# schema.net
KiCad netlist of a schematic drawn in EAGLE
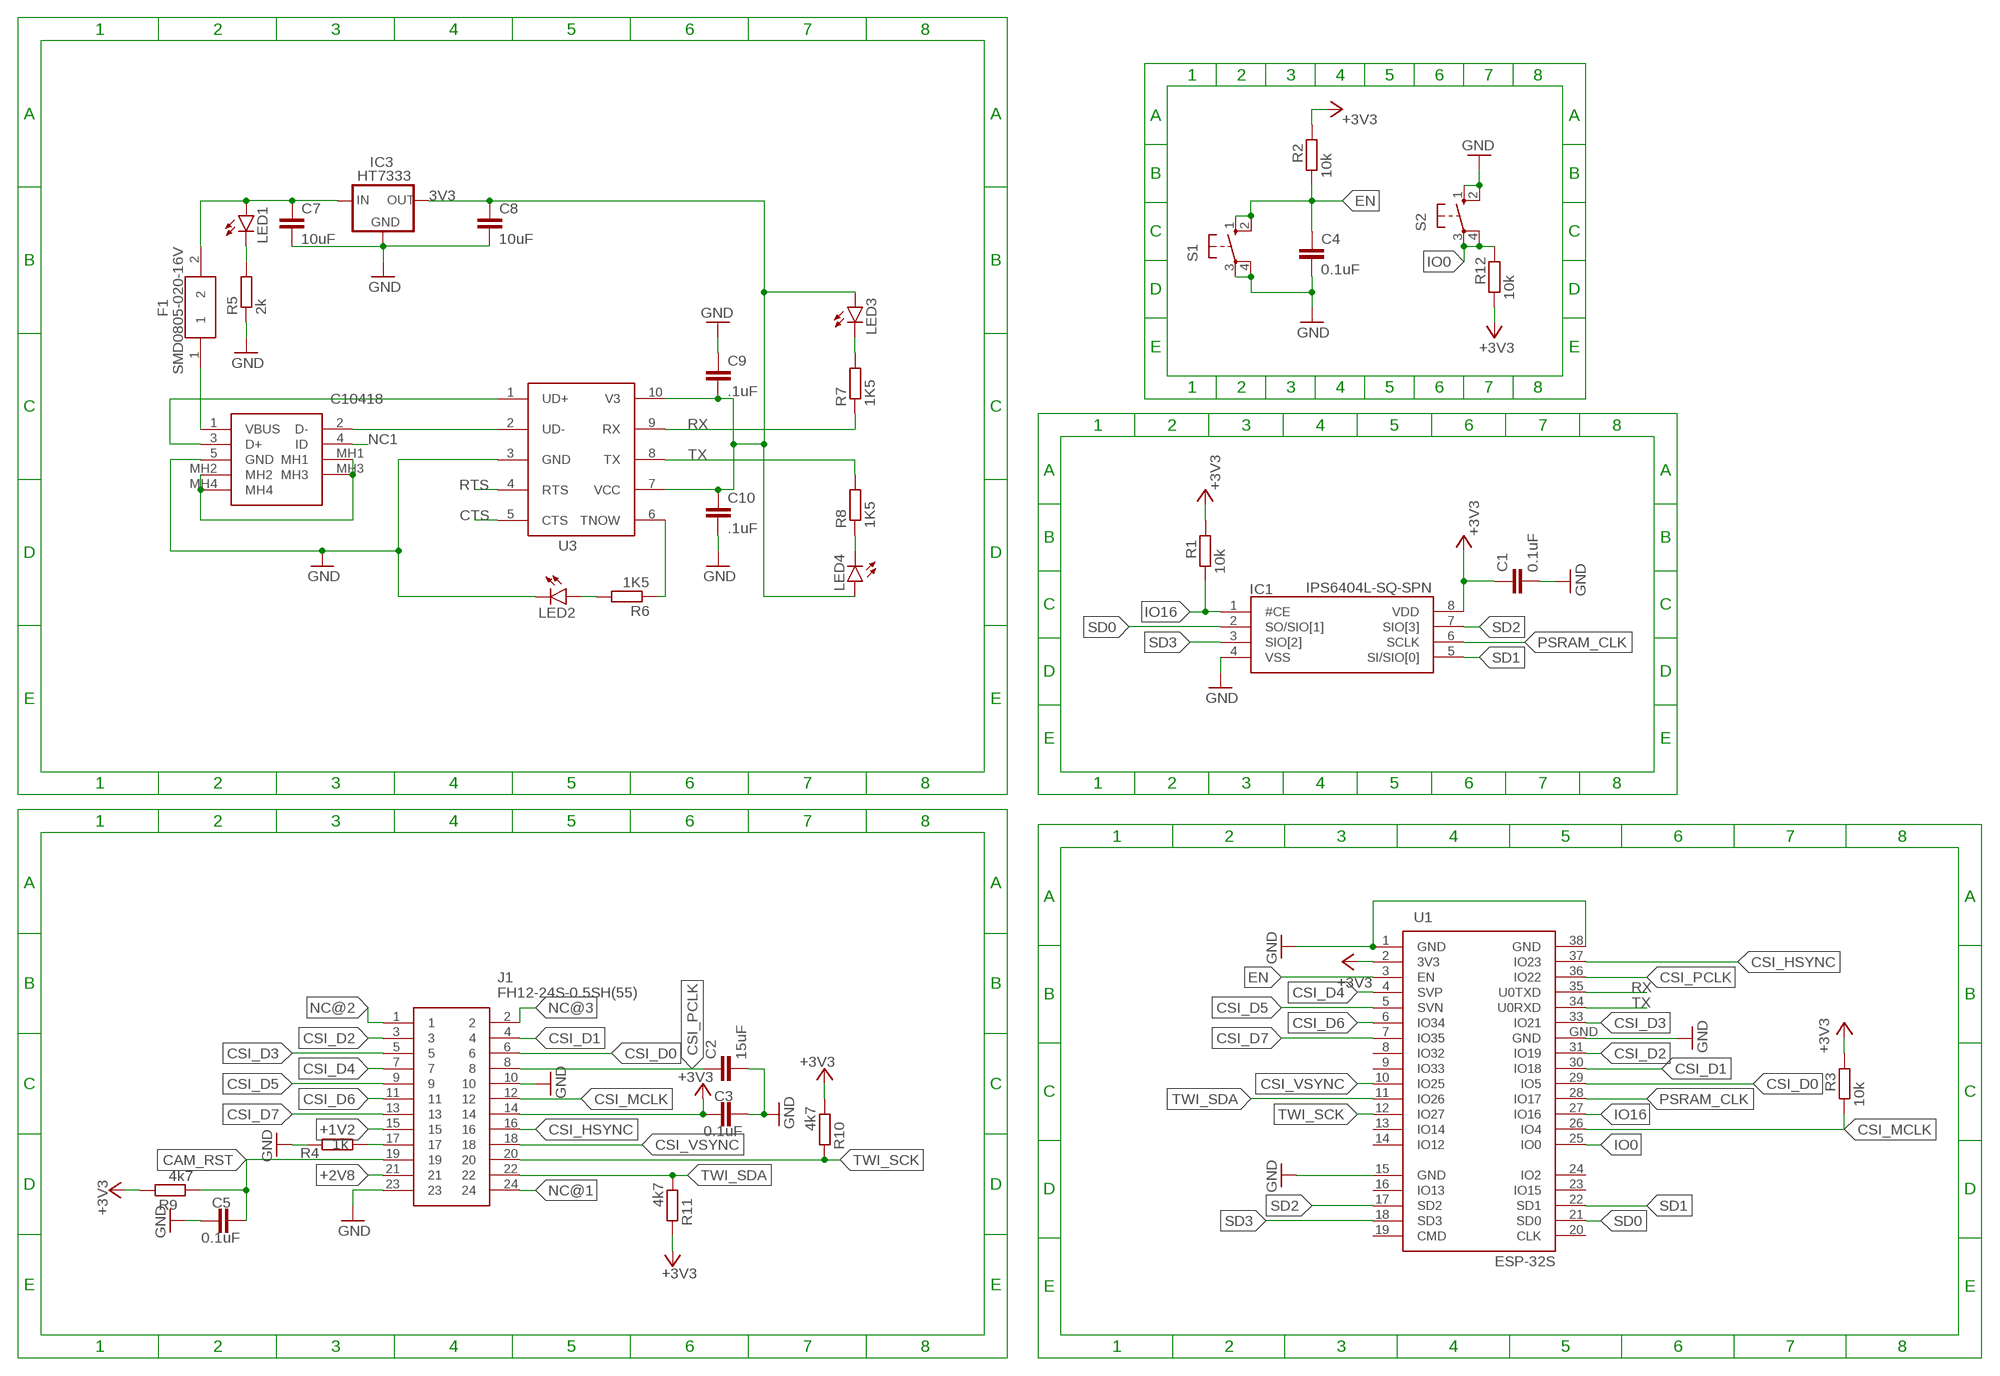
[diagram p0: schematic, sheet 1]

(export (version "E")
  (design (tool "Eeschema 10.0.6"))
  (components
    (comp (ref "C1")
      (value "0.1uF")
      (footprint "eagle-import:C0805")
      (libsource (lib "eagle-import") (part "C-EUC0805"))
    )
    (comp (ref "C2")
      (value "15uF")
      (footprint "eagle-import:C0805")
      (libsource (lib "eagle-import") (part "C-EUC0805"))
    )
    (comp (ref "C3")
      (value "0.1uF")
      (footprint "eagle-import:C0805")
      (libsource (lib "eagle-import") (part "C-EUC0805"))
    )
    (comp (ref "C4")
      (value "0.1uF")
      (footprint "eagle-import:C0805")
      (libsource (lib "eagle-import") (part "C-EUC0805"))
    )
    (comp (ref "C5")
      (value "0.1uF")
      (footprint "eagle-import:C0805")
      (libsource (lib "eagle-import") (part "C-EUC0805"))
    )
    (comp (ref "C7")
      (value "10uF")
      (footprint "eagle-import:C0805")
      (libsource (lib "eagle-import") (part "C-EUC0805"))
    )
    (comp (ref "C8")
      (value "10uF")
      (footprint "eagle-import:C0805")
      (libsource (lib "eagle-import") (part "C-EUC0805"))
    )
    (comp (ref "C9")
      (value ".1uF")
      (footprint "eagle-import:C0805")
      (libsource (lib "eagle-import") (part "C-EUC0805"))
    )
    (comp (ref "C10")
      (value ".1uF")
      (footprint "eagle-import:C0805")
      (libsource (lib "eagle-import") (part "C-EUC0805"))
    )
    (comp (ref "F1")
      (value "SMD0805-020-16V")
      (footprint "eagle-import:FUSC2114X100N")
      (libsource (lib "eagle-import") (part "SMD0805-020-16V"))
    )
    (comp (ref "IC1")
      (value "IPS6404L-SQ-SPN")
      (footprint "eagle-import:SOIC127P600X175-8N")
      (libsource (lib "eagle-import") (part "IPS6404L-SQ-SPN"))
    )
    (comp (ref "IC3")
      (value "HT7333")
      (footprint "eagle-import:SOT-89")
      (libsource (lib "eagle-import") (part "HT7333"))
    )
    (comp (ref "J1")
      (value "FH12-24S-0.5SH(55)")
      (footprint "eagle-import:FH12-24S-0.5SH(55)")
      (fields
        (field (name "MOUSER_PART_NUMBER") "798-FH12-24S-0.5SH55")
        (field (name "RS_PART_NUMBER") "7388827P")
      )
      (libsource (lib "eagle-import") (part "FH12-24S-0.5SH(55)"))
    )
    (comp (ref "J3")
      (value "C10418")
      (footprint "eagle-import:C10418")
      (libsource (lib "eagle-import") (part "C10418"))
    )
    (comp (ref "LED1")
      (value "LEDCHIP-LED0805")
      (footprint "eagle-import:CHIP-LED0805")
      (libsource (lib "eagle-import") (part "LEDCHIP-LED0805"))
    )
    (comp (ref "LED2")
      (value "LEDCHIP-LED0805")
      (footprint "eagle-import:CHIP-LED0805")
      (libsource (lib "eagle-import") (part "LEDCHIP-LED0805"))
    )
    (comp (ref "LED3")
      (value "LEDCHIP-LED0805")
      (footprint "eagle-import:CHIP-LED0805")
      (libsource (lib "eagle-import") (part "LEDCHIP-LED0805"))
    )
    (comp (ref "LED4")
      (value "LEDCHIP-LED0805")
      (footprint "eagle-import:CHIP-LED0805")
      (libsource (lib "eagle-import") (part "LEDCHIP-LED0805"))
    )
    (comp (ref "R1")
      (value "10k")
      (footprint "eagle-import:R0805")
      (libsource (lib "eagle-import") (part "R-EU_R0805"))
    )
    (comp (ref "R2")
      (value "10k")
      (footprint "eagle-import:R0805")
      (libsource (lib "eagle-import") (part "R-EU_R0805"))
    )
    (comp (ref "R3")
      (value "10k")
      (footprint "eagle-import:R0805")
      (libsource (lib "eagle-import") (part "R-EU_R0805"))
    )
    (comp (ref "R4")
      (value "1k")
      (footprint "eagle-import:R0805")
      (libsource (lib "eagle-import") (part "R-EU_R0805"))
    )
    (comp (ref "R5")
      (value "2k")
      (footprint "eagle-import:R0805")
      (libsource (lib "eagle-import") (part "R-EU_R0805"))
    )
    (comp (ref "R6")
      (value "1K5")
      (footprint "eagle-import:R0805")
      (libsource (lib "eagle-import") (part "R-EU_R0805"))
    )
    (comp (ref "R7")
      (value "1K5")
      (footprint "eagle-import:R0805")
      (libsource (lib "eagle-import") (part "R-EU_R0805"))
    )
    (comp (ref "R8")
      (value "1K5")
      (footprint "eagle-import:R0805")
      (libsource (lib "eagle-import") (part "R-EU_R0805"))
    )
    (comp (ref "R9")
      (value "4k7")
      (footprint "eagle-import:R0805")
      (libsource (lib "eagle-import") (part "R-EU_R0805"))
    )
    (comp (ref "R10")
      (value "4k7")
      (footprint "eagle-import:R0805")
      (libsource (lib "eagle-import") (part "R-EU_R0805"))
    )
    (comp (ref "R11")
      (value "4k7")
      (footprint "eagle-import:R0805")
      (libsource (lib "eagle-import") (part "R-EU_R0805"))
    )
    (comp (ref "R12")
      (value "10k")
      (footprint "eagle-import:R0805")
      (libsource (lib "eagle-import") (part "R-EU_R0805"))
    )
    (comp (ref "S1")
      (value "10-XX")
      (footprint "eagle-import:B3F-10XX")
      (fields (field (name "MPN") "B3F-1000"))
      (libsource (lib "eagle-import") (part "10-XX"))
    )
    (comp (ref "S2")
      (value "10-XX")
      (footprint "eagle-import:B3F-10XX")
      (fields (field (name "MPN") "B3F-1000"))
      (libsource (lib "eagle-import") (part "10-XX"))
    )
    (comp (ref "U1")
      (value "ESP-32S")
      (footprint "eagle-import:ESP-32S")
      (libsource (lib "eagle-import") (part "ESP-32S"))
    )
    (comp (ref "U3")
      (value "CH340ESMD")
      (footprint "eagle-import:MSOP10")
      (libsource (lib "eagle-import") (part "CH340ESMD"))
    )
  )
  (nets
    (net (code "1") (name "+1V2") (class "Default")
      (node (ref "J1") (pin "15") (pinfunction "15_15") (pintype "bidirectional"))
    )
    (net (code "2") (name "+2V8") (class "Default")
      (node (ref "J1") (pin "21") (pinfunction "21_21") (pintype "bidirectional"))
    )
    (net (code "3") (name "+3V3") (class "Default")
      (node (ref "C1") (pin "1") (pinfunction "1_1") (pintype "passive"))
      (node (ref "C3") (pin "1") (pinfunction "1_1") (pintype "passive"))
      (node (ref "IC1") (pin "8") (pinfunction "VDD_8") (pintype "bidirectional"))
      (node (ref "J1") (pin "14") (pinfunction "14_14") (pintype "bidirectional"))
      (node (ref "R1") (pin "2") (pinfunction "2_2") (pintype "passive"))
      (node (ref "R10") (pin "1") (pinfunction "1_1") (pintype "passive"))
      (node (ref "R11") (pin "2") (pinfunction "2_2") (pintype "passive"))
      (node (ref "R12") (pin "1") (pinfunction "1_1") (pintype "passive"))
      (node (ref "R2") (pin "2") (pinfunction "2_2") (pintype "passive"))
      (node (ref "R3") (pin "2") (pinfunction "2_2") (pintype "passive"))
      (node (ref "R9") (pin "2") (pinfunction "2_2") (pintype "passive"))
      (node (ref "U1") (pin "2") (pinfunction "3V3_2") (pintype "power_in"))
    )
    (net (code "4") (name "/3V3") (class "Default")
      (node (ref "C10") (pin "1") (pinfunction "1_1") (pintype "passive"))
      (node (ref "C8") (pin "1") (pinfunction "1_1") (pintype "passive"))
      (node (ref "C9") (pin "2") (pinfunction "2_2") (pintype "passive"))
      (node (ref "IC3") (pin "1") (pinfunction "OUT_1") (pintype "passive"))
      (node (ref "LED3") (pin "A") (pinfunction "A_A") (pintype "passive"))
      (node (ref "LED4") (pin "A") (pinfunction "A_A") (pintype "passive"))
      (node (ref "U3") (pin "10") (pinfunction "V3_10") (pintype "power_in"))
      (node (ref "U3") (pin "7") (pinfunction "VCC_7") (pintype "power_in"))
    )
    (net (code "5") (name "/CTS") (class "Default")
      (node (ref "U3") (pin "5") (pinfunction "CTS_5") (pintype "input"))
    )
    (net (code "6") (name "/NC1") (class "Default")
      (node (ref "J3") (pin "4") (pinfunction "ID_4") (pintype "bidirectional"))
    )
    (net (code "7") (name "/RTS") (class "Default")
      (node (ref "U3") (pin "4") (pinfunction "RTS_4") (pintype "output"))
    )
    (net (code "8") (name "/RX") (class "Default")
      (node (ref "R7") (pin "1") (pinfunction "1_1") (pintype "passive"))
      (node (ref "U1") (pin "35") (pinfunction "U0TXD_35") (pintype "bidirectional"))
      (node (ref "U3") (pin "9") (pinfunction "RX_9") (pintype "input"))
    )
    (net (code "9") (name "/TX") (class "Default")
      (node (ref "R8") (pin "2") (pinfunction "2_2") (pintype "passive"))
      (node (ref "U1") (pin "34") (pinfunction "U0RXD_34") (pintype "bidirectional"))
      (node (ref "U3") (pin "8") (pinfunction "TX_8") (pintype "output"))
    )
    (net (code "10") (name "CAM_RST") (class "Default")
      (node (ref "C5") (pin "2") (pinfunction "2_2") (pintype "passive"))
      (node (ref "J1") (pin "19") (pinfunction "19_19") (pintype "bidirectional"))
      (node (ref "R9") (pin "1") (pinfunction "1_1") (pintype "passive"))
    )
    (net (code "11") (name "CSI_D0") (class "Default")
      (node (ref "J1") (pin "6") (pinfunction "6_6") (pintype "bidirectional"))
      (node (ref "U1") (pin "29") (pinfunction "IO5_29") (pintype "bidirectional"))
    )
    (net (code "12") (name "CSI_D1") (class "Default")
      (node (ref "J1") (pin "4") (pinfunction "4_4") (pintype "bidirectional"))
      (node (ref "U1") (pin "30") (pinfunction "IO18_30") (pintype "bidirectional"))
    )
    (net (code "13") (name "CSI_D2") (class "Default")
      (node (ref "J1") (pin "3") (pinfunction "3_3") (pintype "bidirectional"))
      (node (ref "U1") (pin "31") (pinfunction "IO19_31") (pintype "bidirectional"))
    )
    (net (code "14") (name "CSI_D3") (class "Default")
      (node (ref "J1") (pin "5") (pinfunction "5_5") (pintype "bidirectional"))
      (node (ref "U1") (pin "33") (pinfunction "IO21_33") (pintype "bidirectional"))
    )
    (net (code "15") (name "CSI_D4") (class "Default")
      (node (ref "J1") (pin "7") (pinfunction "7_7") (pintype "bidirectional"))
      (node (ref "U1") (pin "4") (pinfunction "SVP_4") (pintype "bidirectional"))
    )
    (net (code "16") (name "CSI_D5") (class "Default")
      (node (ref "J1") (pin "9") (pinfunction "9_9") (pintype "bidirectional"))
      (node (ref "U1") (pin "5") (pinfunction "SVN_5") (pintype "bidirectional"))
    )
    (net (code "17") (name "CSI_D6") (class "Default")
      (node (ref "J1") (pin "11") (pinfunction "11_11") (pintype "bidirectional"))
      (node (ref "U1") (pin "6") (pinfunction "IO34_6") (pintype "bidirectional"))
    )
    (net (code "18") (name "CSI_D7") (class "Default")
      (node (ref "J1") (pin "13") (pinfunction "13_13") (pintype "bidirectional"))
      (node (ref "U1") (pin "7") (pinfunction "IO35_7") (pintype "bidirectional"))
    )
    (net (code "19") (name "CSI_HSYNC") (class "Default")
      (node (ref "J1") (pin "16") (pinfunction "16_16") (pintype "bidirectional"))
      (node (ref "U1") (pin "37") (pinfunction "IO23_37") (pintype "bidirectional"))
    )
    (net (code "20") (name "CSI_MCLK") (class "Default")
      (node (ref "J1") (pin "12") (pinfunction "12_12") (pintype "bidirectional"))
      (node (ref "R3") (pin "1") (pinfunction "1_1") (pintype "passive"))
      (node (ref "U1") (pin "26") (pinfunction "IO4_26") (pintype "bidirectional"))
    )
    (net (code "21") (name "CSI_PCLK") (class "Default")
      (node (ref "C2") (pin "1") (pinfunction "1_1") (pintype "passive"))
      (node (ref "J1") (pin "8") (pinfunction "8_8") (pintype "bidirectional"))
      (node (ref "U1") (pin "36") (pinfunction "IO22_36") (pintype "bidirectional"))
    )
    (net (code "22") (name "CSI_VSYNC") (class "Default")
      (node (ref "J1") (pin "18") (pinfunction "18_18") (pintype "bidirectional"))
      (node (ref "U1") (pin "10") (pinfunction "IO25_10") (pintype "bidirectional"))
    )
    (net (code "23") (name "EN") (class "Default")
      (node (ref "C4") (pin "1") (pinfunction "1_1") (pintype "passive"))
      (node (ref "R2") (pin "1") (pinfunction "1_1") (pintype "passive"))
      (node (ref "S1") (pin "1") (pinfunction "S_1") (pintype "passive"))
      (node (ref "S1") (pin "2") (pinfunction "S1_2") (pintype "passive"))
      (node (ref "U1") (pin "3") (pinfunction "EN_3") (pintype "input"))
    )
    (net (code "24") (name "GND") (class "Default")
      (node (ref "C1") (pin "2") (pinfunction "2_2") (pintype "passive"))
      (node (ref "C10") (pin "2") (pinfunction "2_2") (pintype "passive"))
      (node (ref "C2") (pin "2") (pinfunction "2_2") (pintype "passive"))
      (node (ref "C3") (pin "2") (pinfunction "2_2") (pintype "passive"))
      (node (ref "C4") (pin "2") (pinfunction "2_2") (pintype "passive"))
      (node (ref "C5") (pin "1") (pinfunction "1_1") (pintype "passive"))
      (node (ref "C7") (pin "2") (pinfunction "2_2") (pintype "passive"))
      (node (ref "C8") (pin "2") (pinfunction "2_2") (pintype "passive"))
      (node (ref "C9") (pin "1") (pinfunction "1_1") (pintype "passive"))
      (node (ref "IC1") (pin "4") (pinfunction "VSS_4") (pintype "bidirectional"))
      (node (ref "IC3") (pin "2") (pinfunction "GND_2") (pintype "input"))
      (node (ref "J1") (pin "10") (pinfunction "10_10") (pintype "bidirectional"))
      (node (ref "J1") (pin "23") (pinfunction "23_23") (pintype "bidirectional"))
      (node (ref "J3") (pin "5") (pinfunction "GND_5") (pintype "bidirectional"))
      (node (ref "LED2") (pin "C") (pinfunction "C_C") (pintype "passive"))
      (node (ref "R4") (pin "2") (pinfunction "2_2") (pintype "passive"))
      (node (ref "R5") (pin "1") (pinfunction "1_1") (pintype "passive"))
      (node (ref "S1") (pin "3") (pinfunction "P_3") (pintype "passive"))
      (node (ref "S1") (pin "4") (pinfunction "P1_4") (pintype "passive"))
      (node (ref "S2") (pin "1") (pinfunction "S_1") (pintype "passive"))
      (node (ref "S2") (pin "2") (pinfunction "S1_2") (pintype "passive"))
      (node (ref "U1") (pin "1") (pinfunction "GND_1") (pintype "power_in"))
      (node (ref "U1") (pin "15") (pinfunction "GND_15") (pintype "power_in"))
      (node (ref "U1") (pin "38") (pinfunction "GND_38") (pintype "power_in"))
      (node (ref "U1") (pin "GND") (pinfunction "GND_GND") (pintype "power_in"))
      (node (ref "U3") (pin "3") (pinfunction "GND_3") (pintype "power_in"))
    )
    (net (code "25") (name "IO0") (class "Default")
      (node (ref "R12") (pin "2") (pinfunction "2_2") (pintype "passive"))
      (node (ref "S2") (pin "3") (pinfunction "P_3") (pintype "passive"))
      (node (ref "S2") (pin "4") (pinfunction "P1_4") (pintype "passive"))
      (node (ref "U1") (pin "25") (pinfunction "IO0_25") (pintype "bidirectional"))
    )
    (net (code "26") (name "IO16") (class "Default")
      (node (ref "IC1") (pin "1") (pinfunction "#CE_1") (pintype "bidirectional"))
      (node (ref "R1") (pin "1") (pinfunction "1_1") (pintype "passive"))
      (node (ref "U1") (pin "27") (pinfunction "IO16_27") (pintype "bidirectional"))
    )
    (net (code "27") (name "NC@1") (class "Default")
      (node (ref "J1") (pin "24") (pinfunction "24_24") (pintype "bidirectional"))
    )
    (net (code "28") (name "NC@2") (class "Default")
      (node (ref "J1") (pin "1") (pinfunction "1_1") (pintype "bidirectional"))
    )
    (net (code "29") (name "NC@3") (class "Default")
      (node (ref "J1") (pin "2") (pinfunction "2_2") (pintype "bidirectional"))
    )
    (net (code "30") (name "Net-(C7-Pad1)") (class "Default")
      (node (ref "C7") (pin "1") (pinfunction "1_1") (pintype "passive"))
      (node (ref "F1") (pin "2") (pinfunction "2_2") (pintype "bidirectional"))
      (node (ref "IC3") (pin "3") (pinfunction "IN_3") (pintype "input"))
      (node (ref "IC3") (pin "4") (pinfunction "IN_4") (pintype "input"))
      (node (ref "LED1") (pin "A") (pinfunction "A_A") (pintype "passive"))
    )
    (net (code "31") (name "Net-(J1-Pad17)") (class "Default")
      (node (ref "J1") (pin "17") (pinfunction "17_17") (pintype "bidirectional"))
      (node (ref "R4") (pin "1") (pinfunction "1_1") (pintype "passive"))
    )
    (net (code "32") (name "Net-(J3-D+)") (class "Default")
      (node (ref "J3") (pin "3") (pinfunction "D+_3") (pintype "bidirectional"))
      (node (ref "U3") (pin "1") (pinfunction "UD+_1") (pintype "bidirectional"))
    )
    (net (code "33") (name "Net-(J3-D-)") (class "Default")
      (node (ref "J3") (pin "2") (pinfunction "D-_2") (pintype "bidirectional"))
      (node (ref "U3") (pin "2") (pinfunction "UD-_2") (pintype "bidirectional"))
    )
    (net (code "34") (name "Net-(J3-PadMH1)") (class "Default")
      (node (ref "J3") (pin "MH1") (pinfunction "MH1_MH1") (pintype "bidirectional"))
      (node (ref "J3") (pin "MH2") (pinfunction "MH2_MH2") (pintype "bidirectional"))
      (node (ref "J3") (pin "MH3") (pinfunction "MH3_MH3") (pintype "bidirectional"))
      (node (ref "J3") (pin "MH4") (pinfunction "MH4_MH4") (pintype "bidirectional"))
    )
    (net (code "35") (name "Net-(J3-VBUS)") (class "Default")
      (node (ref "F1") (pin "1") (pinfunction "1_1") (pintype "bidirectional"))
      (node (ref "J3") (pin "1") (pinfunction "VBUS_1") (pintype "bidirectional"))
    )
    (net (code "36") (name "Net-(LED1-PadC)") (class "Default")
      (node (ref "LED1") (pin "C") (pinfunction "C_C") (pintype "passive"))
      (node (ref "R5") (pin "2") (pinfunction "2_2") (pintype "passive"))
    )
    (net (code "37") (name "Net-(LED2-PadA)") (class "Default")
      (node (ref "LED2") (pin "A") (pinfunction "A_A") (pintype "passive"))
      (node (ref "R6") (pin "2") (pinfunction "2_2") (pintype "passive"))
    )
    (net (code "38") (name "Net-(LED3-PadC)") (class "Default")
      (node (ref "LED3") (pin "C") (pinfunction "C_C") (pintype "passive"))
      (node (ref "R7") (pin "2") (pinfunction "2_2") (pintype "passive"))
    )
    (net (code "39") (name "Net-(LED4-PadC)") (class "Default")
      (node (ref "LED4") (pin "C") (pinfunction "C_C") (pintype "passive"))
      (node (ref "R8") (pin "1") (pinfunction "1_1") (pintype "passive"))
    )
    (net (code "40") (name "Net-(U3-TNOW)") (class "Default")
      (node (ref "R6") (pin "1") (pinfunction "1_1") (pintype "passive"))
      (node (ref "U3") (pin "6") (pinfunction "TNOW_6") (pintype "output"))
    )
    (net (code "41") (name "PSRAM_CLK") (class "Default")
      (node (ref "IC1") (pin "6") (pinfunction "SCLK_6") (pintype "bidirectional"))
      (node (ref "U1") (pin "28") (pinfunction "IO17_28") (pintype "bidirectional"))
    )
    (net (code "42") (name "SD0") (class "Default")
      (node (ref "IC1") (pin "2") (pinfunction "SO/SIO[1]_2") (pintype "bidirectional"))
      (node (ref "U1") (pin "21") (pinfunction "SD0_21") (pintype "bidirectional"))
    )
    (net (code "43") (name "SD1") (class "Default")
      (node (ref "IC1") (pin "5") (pinfunction "SI/SIO[0]_5") (pintype "bidirectional"))
      (node (ref "U1") (pin "22") (pinfunction "SD1_22") (pintype "bidirectional"))
    )
    (net (code "44") (name "SD2") (class "Default")
      (node (ref "IC1") (pin "7") (pinfunction "SIO[3]_7") (pintype "bidirectional"))
      (node (ref "U1") (pin "17") (pinfunction "SD2_17") (pintype "bidirectional"))
    )
    (net (code "45") (name "SD3") (class "Default")
      (node (ref "IC1") (pin "3") (pinfunction "SIO[2]_3") (pintype "bidirectional"))
      (node (ref "U1") (pin "18") (pinfunction "SD3_18") (pintype "bidirectional"))
    )
    (net (code "46") (name "TWI_SCK") (class "Default")
      (node (ref "J1") (pin "20") (pinfunction "20_20") (pintype "bidirectional"))
      (node (ref "R10") (pin "2") (pinfunction "2_2") (pintype "passive"))
      (node (ref "U1") (pin "12") (pinfunction "IO27_12") (pintype "bidirectional"))
    )
    (net (code "47") (name "TWI_SDA") (class "Default")
      (node (ref "J1") (pin "22") (pinfunction "22_22") (pintype "bidirectional"))
      (node (ref "R11") (pin "1") (pinfunction "1_1") (pintype "passive"))
      (node (ref "U1") (pin "11") (pinfunction "IO26_11") (pintype "bidirectional"))
    )
    (net (code "48") (name "unconnected-(U1-CLK-Pad20)") (class "Default")
      (node (ref "U1") (pin "20") (pinfunction "CLK_20") (pintype "bidirectional"))
    )
    (net (code "49") (name "unconnected-(U1-CMD-Pad19)") (class "Default")
      (node (ref "U1") (pin "19") (pinfunction "CMD_19") (pintype "bidirectional"))
    )
    (net (code "50") (name "unconnected-(U1-IO2-Pad24)") (class "Default")
      (node (ref "U1") (pin "24") (pinfunction "IO2_24") (pintype "bidirectional"))
    )
    (net (code "51") (name "unconnected-(U1-IO12-Pad14)") (class "Default")
      (node (ref "U1") (pin "14") (pinfunction "IO12_14") (pintype "bidirectional"))
    )
    (net (code "52") (name "unconnected-(U1-IO13-Pad16)") (class "Default")
      (node (ref "U1") (pin "16") (pinfunction "IO13_16") (pintype "bidirectional"))
    )
    (net (code "53") (name "unconnected-(U1-IO14-Pad13)") (class "Default")
      (node (ref "U1") (pin "13") (pinfunction "IO14_13") (pintype "bidirectional"))
    )
    (net (code "54") (name "unconnected-(U1-IO15-Pad23)") (class "Default")
      (node (ref "U1") (pin "23") (pinfunction "IO15_23") (pintype "bidirectional"))
    )
    (net (code "55") (name "unconnected-(U1-IO32-Pad8)") (class "Default")
      (node (ref "U1") (pin "8") (pinfunction "IO32_8") (pintype "bidirectional"))
    )
    (net (code "56") (name "unconnected-(U1-IO33-Pad9)") (class "Default")
      (node (ref "U1") (pin "9") (pinfunction "IO33_9") (pintype "bidirectional"))
    )
  )
)
